# placa_esp.net
KiCad netlist of a schematic drawn in EAGLE
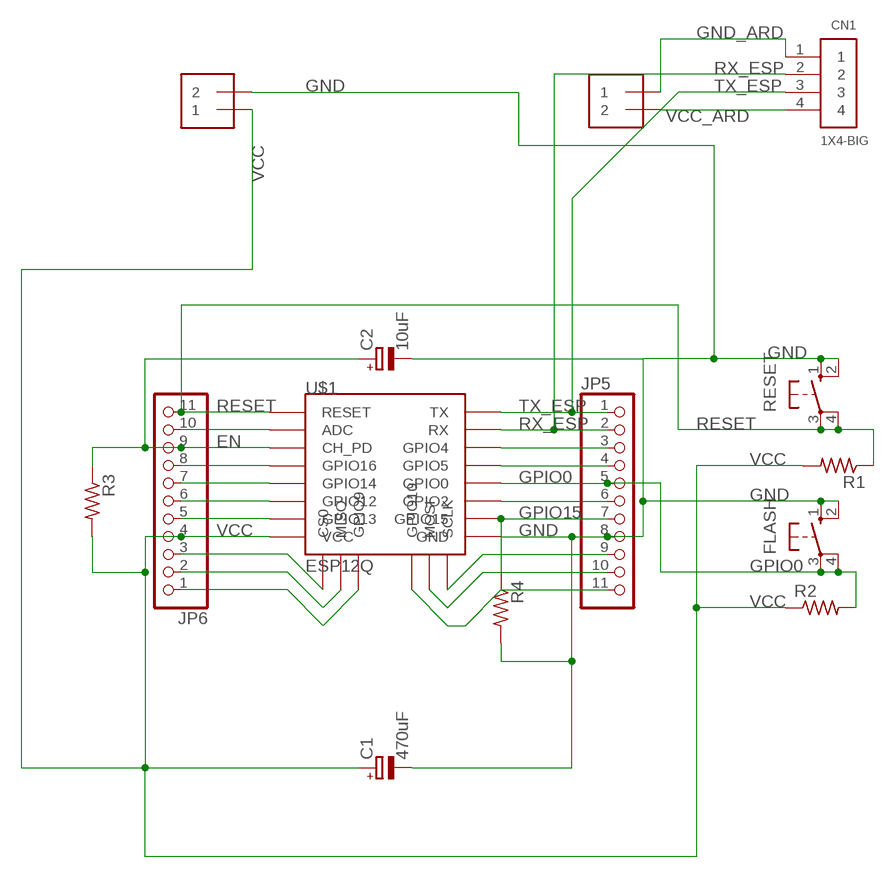
[diagram p0: schematic, sheet 1]

(export (version "E")
  (design (tool "Eeschema 10.0.6"))
  (components
    (comp (ref "C1")
      (value "470uF")
      (footprint "eagle-import:E5-5")
      (libsource (lib "eagle-import") (part "CPOL-EUE5-5"))
    )
    (comp (ref "C2")
      (value "10uF")
      (footprint "eagle-import:E3,5-8")
      (libsource (lib "eagle-import") (part "CPOL-EUE3.5-8"))
    )
    (comp (ref "CN1")
      (value "1X4-BIG")
      (footprint "eagle-import:1X04-BIG")
      (libsource (lib "eagle-import") (part "1X4-BIG"))
    )
    (comp (ref "FLASH")
      (value "10-XX")
      (footprint "eagle-import:B3F-10XX")
      (fields (field (name "MPN") "B3F-1000"))
      (libsource (lib "eagle-import") (part "10-XX"))
    )
    (comp (ref "J1")
      (value "1X2-3.5MM")
      (footprint "eagle-import:1X2-3.5MM")
      (libsource (lib "eagle-import") (part "1X2-3.5MM"))
    )
    (comp (ref "J2")
      (value "1X2-3.5MM")
      (footprint "eagle-import:1X2-3.5MM")
      (libsource (lib "eagle-import") (part "1X2-3.5MM"))
    )
    (comp (ref "JP5")
      (value "PINHD-1X11")
      (footprint "eagle-import:1X11")
      (libsource (lib "eagle-import") (part "PINHD-1X11"))
    )
    (comp (ref "JP6")
      (value "PINHD-1X11")
      (footprint "eagle-import:1X11")
      (libsource (lib "eagle-import") (part "PINHD-1X11"))
    )
    (comp (ref "R1")
      (value "R-US_0204/5")
      (footprint "eagle-import:0204_5")
      (libsource (lib "eagle-import") (part "R-US_0204/5"))
    )
    (comp (ref "R2")
      (value "R-US_0204/5")
      (footprint "eagle-import:0204_5")
      (libsource (lib "eagle-import") (part "R-US_0204/5"))
    )
    (comp (ref "R3")
      (value "R-US_0204/5")
      (footprint "eagle-import:0204_5")
      (libsource (lib "eagle-import") (part "R-US_0204/5"))
    )
    (comp (ref "R4")
      (value "R-US_0204/5")
      (footprint "eagle-import:0204_5")
      (libsource (lib "eagle-import") (part "R-US_0204/5"))
    )
    (comp (ref "RESET")
      (value "10-XX")
      (footprint "eagle-import:B3F-10XX")
      (fields (field (name "MPN") "B3F-1000"))
      (libsource (lib "eagle-import") (part "10-XX"))
    )
    (comp (ref "U$1")
      (value "ESP12Q")
      (footprint "eagle-import:ESP12Q")
      (libsource (lib "eagle-import") (part "ESP12Q"))
    )
  )
  (nets
    (net (code "1") (name "/EN") (class "Default")
      (node (ref "C2") (pin "+") (pinfunction "+_+") (pintype "passive"))
      (node (ref "JP6") (pin "9") (pinfunction "9_9") (pintype "passive"))
      (node (ref "R3") (pin "1") (pinfunction "1_1") (pintype "passive"))
      (node (ref "U$1") (pin "CH_PD") (pinfunction "CH_PD_CH_PD") (pintype "bidirectional"))
    )
    (net (code "2") (name "/GND") (class "Default")
      (node (ref "C1") (pin "-") (pinfunction "-_-") (pintype "passive"))
      (node (ref "C2") (pin "-") (pinfunction "-_-") (pintype "passive"))
      (node (ref "FLASH") (pin "1") (pinfunction "S_1") (pintype "passive"))
      (node (ref "FLASH") (pin "2") (pinfunction "S1_2") (pintype "passive"))
      (node (ref "J2") (pin "2") (pinfunction "2_2") (pintype "passive"))
      (node (ref "JP5") (pin "8") (pinfunction "8_8") (pintype "passive"))
      (node (ref "R4") (pin "2") (pinfunction "2_2") (pintype "passive"))
      (node (ref "RESET") (pin "1") (pinfunction "S_1") (pintype "passive"))
      (node (ref "RESET") (pin "2") (pinfunction "S1_2") (pintype "passive"))
      (node (ref "U$1") (pin "GND") (pinfunction "GND_GND") (pintype "bidirectional"))
    )
    (net (code "3") (name "/GND_ARD") (class "Default")
      (node (ref "CN1") (pin "1") (pinfunction "1_1") (pintype "bidirectional"))
      (node (ref "J1") (pin "1") (pinfunction "1_1") (pintype "passive"))
    )
    (net (code "4") (name "/GPIO0") (class "Default")
      (node (ref "FLASH") (pin "3") (pinfunction "P_3") (pintype "passive"))
      (node (ref "FLASH") (pin "4") (pinfunction "P1_4") (pintype "passive"))
      (node (ref "JP5") (pin "5") (pinfunction "5_5") (pintype "passive"))
      (node (ref "R2") (pin "2") (pinfunction "2_2") (pintype "passive"))
      (node (ref "U$1") (pin "GPIO0") (pinfunction "GPIO0_GPIO0") (pintype "bidirectional"))
    )
    (net (code "5") (name "/GPIO15") (class "Default")
      (node (ref "JP5") (pin "7") (pinfunction "7_7") (pintype "passive"))
      (node (ref "R4") (pin "1") (pinfunction "1_1") (pintype "passive"))
      (node (ref "U$1") (pin "GPIO15") (pinfunction "GPIO15_GPIO15") (pintype "bidirectional"))
    )
    (net (code "6") (name "/RESET") (class "Default")
      (node (ref "JP6") (pin "11") (pinfunction "11_11") (pintype "passive"))
      (node (ref "R1") (pin "1") (pinfunction "1_1") (pintype "passive"))
      (node (ref "RESET") (pin "3") (pinfunction "P_3") (pintype "passive"))
      (node (ref "RESET") (pin "4") (pinfunction "P1_4") (pintype "passive"))
      (node (ref "U$1") (pin "RESET") (pinfunction "RESET_RESET") (pintype "bidirectional"))
    )
    (net (code "7") (name "/RX_ESP") (class "Default")
      (node (ref "CN1") (pin "2") (pinfunction "2_2") (pintype "bidirectional"))
      (node (ref "JP5") (pin "2") (pinfunction "2_2") (pintype "passive"))
      (node (ref "U$1") (pin "RX") (pinfunction "RX_RX") (pintype "bidirectional"))
    )
    (net (code "8") (name "/TX_ESP") (class "Default")
      (node (ref "CN1") (pin "3") (pinfunction "3_3") (pintype "bidirectional"))
      (node (ref "JP5") (pin "1") (pinfunction "1_1") (pintype "passive"))
      (node (ref "U$1") (pin "TX") (pinfunction "TX_TX") (pintype "bidirectional"))
    )
    (net (code "9") (name "/VCC") (class "Default")
      (node (ref "C1") (pin "+") (pinfunction "+_+") (pintype "passive"))
      (node (ref "J2") (pin "1") (pinfunction "1_1") (pintype "passive"))
      (node (ref "JP6") (pin "4") (pinfunction "4_4") (pintype "passive"))
      (node (ref "R1") (pin "2") (pinfunction "2_2") (pintype "passive"))
      (node (ref "R2") (pin "1") (pinfunction "1_1") (pintype "passive"))
      (node (ref "R3") (pin "2") (pinfunction "2_2") (pintype "passive"))
      (node (ref "U$1") (pin "VCC") (pinfunction "VCC_VCC") (pintype "bidirectional"))
    )
    (net (code "10") (name "/VCC_ARD") (class "Default")
      (node (ref "CN1") (pin "4") (pinfunction "4_4") (pintype "bidirectional"))
      (node (ref "J1") (pin "2") (pinfunction "2_2") (pintype "passive"))
    )
    (net (code "11") (name "Net-(JP5-Pad3)") (class "Default")
      (node (ref "JP5") (pin "3") (pinfunction "3_3") (pintype "passive"))
      (node (ref "U$1") (pin "GPIO4") (pinfunction "GPIO4_GPIO4") (pintype "bidirectional"))
    )
    (net (code "12") (name "Net-(JP5-Pad4)") (class "Default")
      (node (ref "JP5") (pin "4") (pinfunction "4_4") (pintype "passive"))
      (node (ref "U$1") (pin "GPIO5") (pinfunction "GPIO5_GPIO5") (pintype "bidirectional"))
    )
    (net (code "13") (name "Net-(JP5-Pad6)") (class "Default")
      (node (ref "JP5") (pin "6") (pinfunction "6_6") (pintype "passive"))
      (node (ref "U$1") (pin "GPIO2") (pinfunction "GPIO2_GPIO2") (pintype "bidirectional"))
    )
    (net (code "14") (name "Net-(JP5-Pad9)") (class "Default")
      (node (ref "JP5") (pin "9") (pinfunction "9_9") (pintype "passive"))
      (node (ref "U$1") (pin "SCLK") (pinfunction "SCLK_SCLK") (pintype "bidirectional"))
    )
    (net (code "15") (name "Net-(JP5-Pad10)") (class "Default")
      (node (ref "JP5") (pin "10") (pinfunction "10_10") (pintype "passive"))
      (node (ref "U$1") (pin "MOSI") (pinfunction "MOSI_MOSI") (pintype "bidirectional"))
    )
    (net (code "16") (name "Net-(JP5-Pad11)") (class "Default")
      (node (ref "JP5") (pin "11") (pinfunction "11_11") (pintype "passive"))
      (node (ref "U$1") (pin "GPIO10") (pinfunction "GPIO10_GPIO10") (pintype "bidirectional"))
    )
    (net (code "17") (name "Net-(JP6-Pad1)") (class "Default")
      (node (ref "JP6") (pin "1") (pinfunction "1_1") (pintype "passive"))
      (node (ref "U$1") (pin "GPIO9") (pinfunction "GPIO9_GPIO9") (pintype "bidirectional"))
    )
    (net (code "18") (name "Net-(JP6-Pad2)") (class "Default")
      (node (ref "JP6") (pin "2") (pinfunction "2_2") (pintype "passive"))
      (node (ref "U$1") (pin "MISO") (pinfunction "MISO_MISO") (pintype "bidirectional"))
    )
    (net (code "19") (name "Net-(JP6-Pad3)") (class "Default")
      (node (ref "JP6") (pin "3") (pinfunction "3_3") (pintype "passive"))
      (node (ref "U$1") (pin "CS0") (pinfunction "CS0_CS0") (pintype "bidirectional"))
    )
    (net (code "20") (name "Net-(JP6-Pad5)") (class "Default")
      (node (ref "JP6") (pin "5") (pinfunction "5_5") (pintype "passive"))
      (node (ref "U$1") (pin "GPIO13") (pinfunction "GPIO13_GPIO13") (pintype "bidirectional"))
    )
    (net (code "21") (name "Net-(JP6-Pad6)") (class "Default")
      (node (ref "JP6") (pin "6") (pinfunction "6_6") (pintype "passive"))
      (node (ref "U$1") (pin "GPIO12") (pinfunction "GPIO12_GPIO12") (pintype "bidirectional"))
    )
    (net (code "22") (name "Net-(JP6-Pad7)") (class "Default")
      (node (ref "JP6") (pin "7") (pinfunction "7_7") (pintype "passive"))
      (node (ref "U$1") (pin "GPIO14") (pinfunction "GPIO14_GPIO14") (pintype "bidirectional"))
    )
    (net (code "23") (name "Net-(JP6-Pad8)") (class "Default")
      (node (ref "JP6") (pin "8") (pinfunction "8_8") (pintype "passive"))
      (node (ref "U$1") (pin "GPIO16") (pinfunction "GPIO16_GPIO16") (pintype "bidirectional"))
    )
    (net (code "24") (name "Net-(JP6-Pad10)") (class "Default")
      (node (ref "JP6") (pin "10") (pinfunction "10_10") (pintype "passive"))
      (node (ref "U$1") (pin "ADC") (pinfunction "ADC_ADC") (pintype "bidirectional"))
    )
  )
)
